# GSM_Modem_Power_Feed.net
KiCad netlist of a schematic drawn in Altium Designer
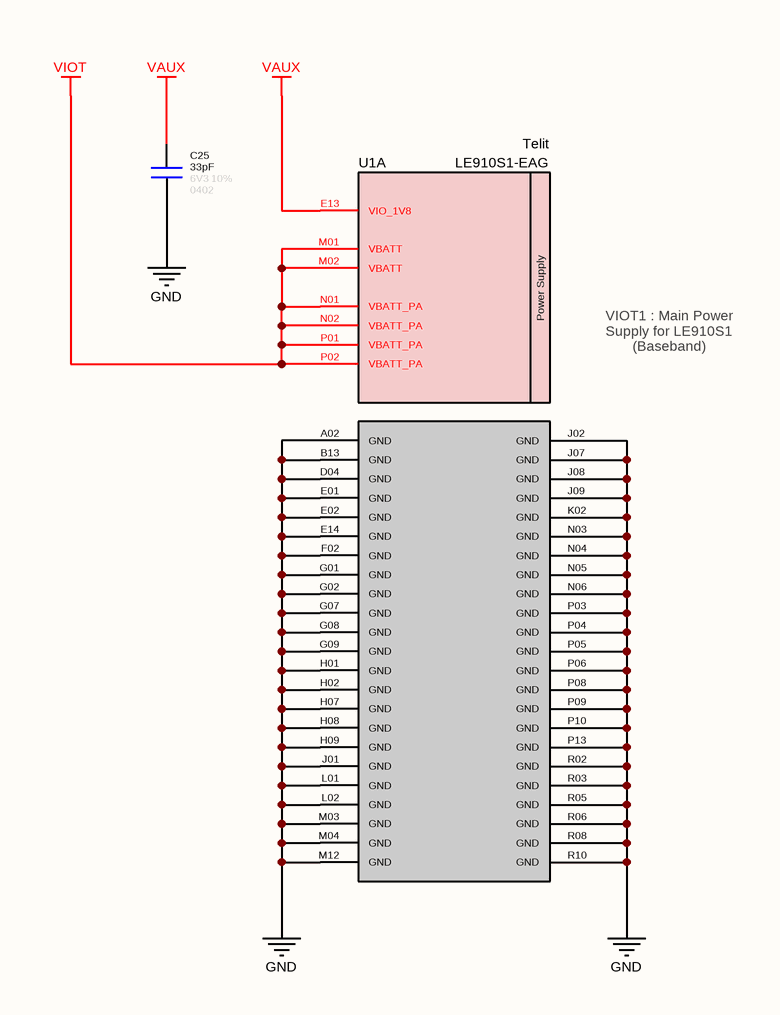
[diagram p0: GSM Modem Power Feed.SchDoc]

(export (version "E")
  (design (tool "Eeschema 10.0.6"))
  (components
    (comp (ref "C25")
      (value "33pF")
      (footprint "CAPACITOR_0402")
      (description "Capacitor - 33pF [0402] (Ceramic)")
      (fields
        (field (name "MANUFACTURER PART NUMBER") "C0402C330J9RACAUTO")
        (field (name "TOLERANCE") "10%")
        (field (name "CASE") "0402")
        (field (name "VOLTAGE") "6V3")
      )
      (libsource (lib "P101DA_Library") (part "Capacitor - 33pF [0402-6V3]"))
    )
    (comp (ref "U1")
      (value "LE910S1-EAG LTE GSM Module")
      (footprint "LE910 GSM Modem")
      (description "Telit LE910S1-EAG GPRS/GNSS Module")
      (fields
        (field (name "MANUFACTURER PART NUMBER") "LE910S1-EAG")
        (field (name "MANUFACTURER NAME") "Telit")
      )
      (libsource (lib "P101DA_Library") (part "IC - LE910S1-EAG"))
    )
  )
  (nets
    (net (code "1") (name "GND") (class "Default")
      (node (ref "C25") (pin "1") (pinfunction "1_1") (pintype "passive"))
      (node (ref "U1") (pin "A02") (pinfunction "GND_A02") (pintype "power_in"))
      (node (ref "U1") (pin "B13") (pinfunction "GND_B13") (pintype "power_in"))
      (node (ref "U1") (pin "D04") (pinfunction "GND_D04") (pintype "power_in"))
      (node (ref "U1") (pin "E01") (pinfunction "GND_E01") (pintype "power_in"))
      (node (ref "U1") (pin "E02") (pinfunction "GND_E02") (pintype "power_in"))
      (node (ref "U1") (pin "E14") (pinfunction "GND_E14") (pintype "power_in"))
      (node (ref "U1") (pin "F02") (pinfunction "GND_F02") (pintype "power_in"))
      (node (ref "U1") (pin "G01") (pinfunction "GND_G01") (pintype "power_in"))
      (node (ref "U1") (pin "G02") (pinfunction "GND_G02") (pintype "power_in"))
      (node (ref "U1") (pin "G07") (pinfunction "GND_G07") (pintype "power_in"))
      (node (ref "U1") (pin "G08") (pinfunction "GND_G08") (pintype "power_in"))
      (node (ref "U1") (pin "G09") (pinfunction "GND_G09") (pintype "power_in"))
      (node (ref "U1") (pin "H01") (pinfunction "GND_H01") (pintype "power_in"))
      (node (ref "U1") (pin "H02") (pinfunction "GND_H02") (pintype "power_in"))
      (node (ref "U1") (pin "H07") (pinfunction "GND_H07") (pintype "power_in"))
      (node (ref "U1") (pin "H08") (pinfunction "GND_H08") (pintype "power_in"))
      (node (ref "U1") (pin "H09") (pinfunction "GND_H09") (pintype "power_in"))
      (node (ref "U1") (pin "J01") (pinfunction "GND_J01") (pintype "power_in"))
      (node (ref "U1") (pin "J02") (pinfunction "GND_J02") (pintype "power_in"))
      (node (ref "U1") (pin "J07") (pinfunction "GND_J07") (pintype "power_in"))
      (node (ref "U1") (pin "J08") (pinfunction "GND_J08") (pintype "power_in"))
      (node (ref "U1") (pin "J09") (pinfunction "GND_J09") (pintype "power_in"))
      (node (ref "U1") (pin "K02") (pinfunction "GND_K02") (pintype "power_in"))
      (node (ref "U1") (pin "L01") (pinfunction "GND_L01") (pintype "power_in"))
      (node (ref "U1") (pin "L02") (pinfunction "GND_L02") (pintype "power_in"))
      (node (ref "U1") (pin "M03") (pinfunction "GND_M03") (pintype "power_in"))
      (node (ref "U1") (pin "M04") (pinfunction "GND_M04") (pintype "power_in"))
      (node (ref "U1") (pin "M12") (pinfunction "GND_M12") (pintype "power_in"))
      (node (ref "U1") (pin "N03") (pinfunction "GND_N03") (pintype "power_in"))
      (node (ref "U1") (pin "N04") (pinfunction "GND_N04") (pintype "power_in"))
      (node (ref "U1") (pin "N05") (pinfunction "GND_N05") (pintype "power_in"))
      (node (ref "U1") (pin "N06") (pinfunction "GND_N06") (pintype "power_in"))
      (node (ref "U1") (pin "P03") (pinfunction "GND_P03") (pintype "power_in"))
      (node (ref "U1") (pin "P04") (pinfunction "GND_P04") (pintype "power_in"))
      (node (ref "U1") (pin "P05") (pinfunction "GND_P05") (pintype "power_in"))
      (node (ref "U1") (pin "P06") (pinfunction "GND_P06") (pintype "power_in"))
      (node (ref "U1") (pin "P08") (pinfunction "GND_P08") (pintype "power_in"))
      (node (ref "U1") (pin "P09") (pinfunction "GND_P09") (pintype "power_in"))
      (node (ref "U1") (pin "P10") (pinfunction "GND_P10") (pintype "power_in"))
      (node (ref "U1") (pin "P13") (pinfunction "GND_P13") (pintype "power_in"))
      (node (ref "U1") (pin "R02") (pinfunction "GND_R02") (pintype "power_in"))
      (node (ref "U1") (pin "R03") (pinfunction "GND_R03") (pintype "power_in"))
      (node (ref "U1") (pin "R05") (pinfunction "GND_R05") (pintype "power_in"))
      (node (ref "U1") (pin "R06") (pinfunction "GND_R06") (pintype "power_in"))
      (node (ref "U1") (pin "R08") (pinfunction "GND_R08") (pintype "power_in"))
      (node (ref "U1") (pin "R10") (pinfunction "GND_R10") (pintype "power_in"))
    )
    (net (code "2") (name "VAUX") (class "Default")
      (node (ref "C25") (pin "2") (pinfunction "2_2") (pintype "passive"))
      (node (ref "U1") (pin "E13") (pinfunction "VIO_1V8_E13") (pintype "power_in"))
    )
    (net (code "3") (name "VIOT") (class "Default")
      (node (ref "U1") (pin "M01") (pinfunction "VBATT_M01") (pintype "power_in"))
      (node (ref "U1") (pin "M02") (pinfunction "VBATT_M02") (pintype "power_in"))
      (node (ref "U1") (pin "N01") (pinfunction "VBATT_PA_N01") (pintype "power_in"))
      (node (ref "U1") (pin "N02") (pinfunction "VBATT_PA_N02") (pintype "power_in"))
      (node (ref "U1") (pin "P01") (pinfunction "VBATT_PA_P01") (pintype "power_in"))
      (node (ref "U1") (pin "P02") (pinfunction "VBATT_PA_P02") (pintype "power_in"))
    )
  )
)
